# BLDC_Driver_1_1.net
KiCad netlist of a schematic drawn in Altium Designer
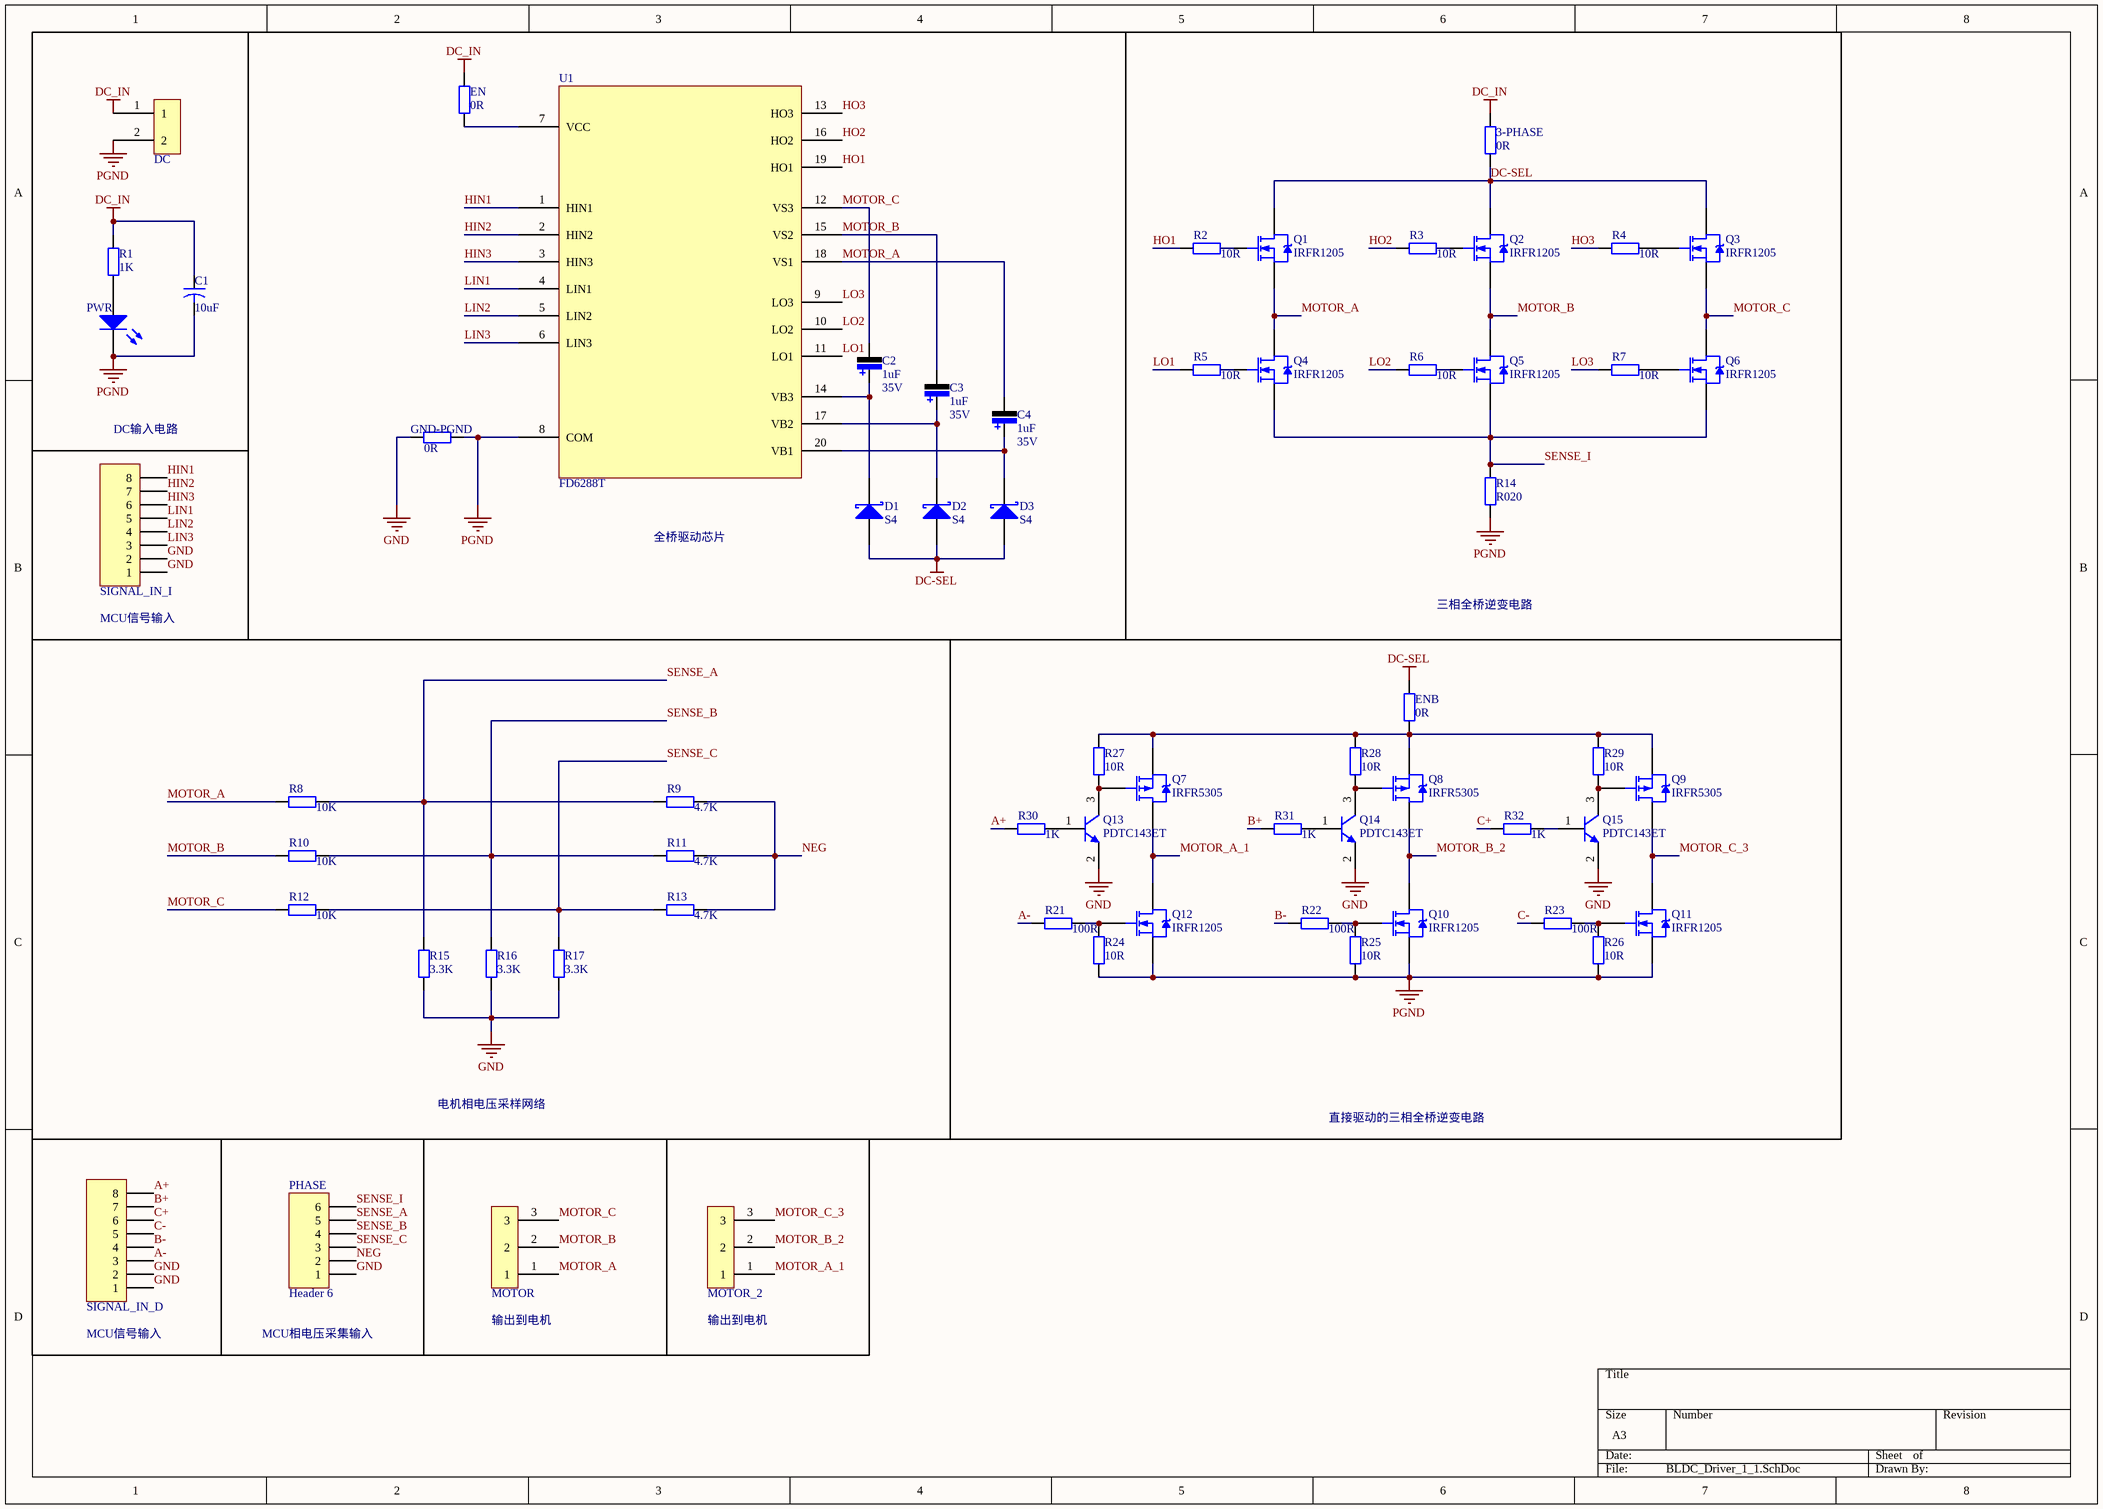
[diagram p0: BLDC_Driver_1_1.SchDoc]

(export (version "E")
  (design (tool "Eeschema 10.0.6"))
  (components
    (comp (ref "3-PHASE")
      (value "0R")
      (footprint "0805-2")
      (description "Resistor")
      (fields (field (name "Comment") "Res2") (field (name "PUBLISHER") "Altium Limited"))
      (libsource (lib "Miscellaneous Devices") (part "Res2"))
    )
    (comp (ref "C1")
      (value "10uF")
      (footprint "CAPR5-4X5")
      (description "Capacitor")
      (fields (field (name "Comment") "Cap2") (field (name "PUBLISHER") "Altium Limited"))
      (libsource (lib "Miscellaneous Devices") (part "Cap2"))
    )
    (comp (ref "C2")
      (value "1uF")
      (footprint "CAP-3216")
      (description "极性电解电容")
      (fields
        (field (name "VOL") "35V")
        (field (name "Comment") "Cap Pol")
        (field (name "PUBLISHER") "Altium Limited")
      )
      (libsource (lib "Fszhang") (part "Cap Pol"))
    )
    (comp (ref "C3")
      (value "1uF")
      (footprint "CAP-3216")
      (description "极性电解电容")
      (fields
        (field (name "VOL") "35V")
        (field (name "Comment") "Cap Pol")
        (field (name "PUBLISHER") "Altium Limited")
      )
      (libsource (lib "Fszhang") (part "Cap Pol"))
    )
    (comp (ref "C4")
      (value "1uF")
      (footprint "CAP-3216")
      (description "极性电解电容")
      (fields
        (field (name "VOL") "35V")
        (field (name "Comment") "Cap Pol")
        (field (name "PUBLISHER") "Altium Limited")
      )
      (libsource (lib "Fszhang") (part "Cap Pol"))
    )
    (comp (ref "D1")
      (value "D-Schottky")
      (footprint "DIODE-1206")
      (description "肖特基二极管")
      (fields (field (name "TYPE") "S4") (field (name "PUBLISHER") "Altium Limited"))
      (libsource (lib "Fszhang") (part "D-Schottky"))
    )
    (comp (ref "D2")
      (value "D-Schottky")
      (footprint "DIODE-1206")
      (description "肖特基二极管")
      (fields (field (name "TYPE") "S4") (field (name "PUBLISHER") "Altium Limited"))
      (libsource (lib "Fszhang") (part "D-Schottky"))
    )
    (comp (ref "D3")
      (value "D-Schottky")
      (footprint "DIODE-1206")
      (description "肖特基二极管")
      (fields (field (name "TYPE") "S4") (field (name "PUBLISHER") "Altium Limited"))
      (libsource (lib "Fszhang") (part "D-Schottky"))
    )
    (comp (ref "DC") (value "JXZ2") (footprint "JXZ2") (libsource (lib "Connector") (part "JXZ2")))
    (comp (ref "EN")
      (value "0R")
      (footprint "0805-2")
      (description "Resistor")
      (fields (field (name "Comment") "Res2") (field (name "PUBLISHER") "Altium Limited"))
      (libsource (lib "Miscellaneous Devices") (part "Res2"))
    )
    (comp (ref "ENB")
      (value "0R")
      (footprint "0805-2")
      (description "Resistor")
      (fields (field (name "Comment") "Res2") (field (name "PUBLISHER") "Altium Limited"))
      (libsource (lib "Miscellaneous Devices") (part "Res2"))
    )
    (comp (ref "GND-PGND")
      (value "0R")
      (footprint "1206")
      (description "Resistor")
      (fields (field (name "Comment") "Res2") (field (name "PUBLISHER") "Altium Limited"))
      (libsource (lib "") (part "Res2_2"))
    )
    (comp (ref "MOTOR") (value "JXZ3") (footprint "JXZ_3") (libsource (lib "Connector") (part "JXZ3")))
    (comp (ref "MOTOR_2") (value "JXZ3") (footprint "JXZ_3") (libsource (lib "Connector") (part "JXZ3")))
    (comp (ref "PHASE")
      (value "Header 6")
      (footprint "HDR1X6")
      (description "Header, 6-Pin")
      (fields (field (name "PUBLISHER") "Altium Limited"))
      (libsource (lib "Miscellaneous Connectors") (part "Header 6"))
    )
    (comp (ref "PWR")
      (value "LED2")
      (footprint "DIODE-1206")
      (description "Typical RED, GREEN, YELLOW, AMBER GaAs LED")
      (fields (field (name "PUBLISHER") "Altium Limited"))
      (libsource (lib "Miscellaneous Devices") (part "LED2"))
    )
    (comp (ref "Q1")
      (value "IRFR1205")
      (footprint "TO-252AA_N")
      (description "HEXFET Power MOSFET")
      (fields (field (name "PUBLISHER") "Altium Limited"))
      (libsource (lib "IR Discrete MOSFET - Power") (part "IRFR1205"))
    )
    (comp (ref "Q2")
      (value "IRFR1205")
      (footprint "TO-252AA_N")
      (description "HEXFET Power MOSFET")
      (fields (field (name "PUBLISHER") "Altium Limited"))
      (libsource (lib "IR Discrete MOSFET - Power") (part "IRFR1205"))
    )
    (comp (ref "Q3")
      (value "IRFR1205")
      (footprint "TO-252AA_N")
      (description "HEXFET Power MOSFET")
      (fields (field (name "PUBLISHER") "Altium Limited"))
      (libsource (lib "IR Discrete MOSFET - Power") (part "IRFR1205"))
    )
    (comp (ref "Q4")
      (value "IRFR1205")
      (footprint "TO-252AA_N")
      (description "HEXFET Power MOSFET")
      (fields (field (name "PUBLISHER") "Altium Limited"))
      (libsource (lib "IR Discrete MOSFET - Power") (part "IRFR1205"))
    )
    (comp (ref "Q5")
      (value "IRFR1205")
      (footprint "TO-252AA_N")
      (description "HEXFET Power MOSFET")
      (fields (field (name "PUBLISHER") "Altium Limited"))
      (libsource (lib "IR Discrete MOSFET - Power") (part "IRFR1205"))
    )
    (comp (ref "Q6")
      (value "IRFR1205")
      (footprint "TO-252AA_N")
      (description "HEXFET Power MOSFET")
      (fields (field (name "PUBLISHER") "Altium Limited"))
      (libsource (lib "IR Discrete MOSFET - Power") (part "IRFR1205"))
    )
    (comp (ref "Q7")
      (value "IRFR5305")
      (footprint "TO-252AA_N")
      (description "HEXFET Power MOSFET")
      (fields (field (name "PUBLISHER") "Altium Limited"))
      (libsource (lib "IR Discrete MOSFET - Power") (part "IRFR5305"))
    )
    (comp (ref "Q8")
      (value "IRFR5305")
      (footprint "TO-252AA_N")
      (description "HEXFET Power MOSFET")
      (fields (field (name "PUBLISHER") "Altium Limited"))
      (libsource (lib "IR Discrete MOSFET - Power") (part "IRFR5305"))
    )
    (comp (ref "Q9")
      (value "IRFR5305")
      (footprint "TO-252AA_N")
      (description "HEXFET Power MOSFET")
      (fields (field (name "PUBLISHER") "Altium Limited"))
      (libsource (lib "IR Discrete MOSFET - Power") (part "IRFR5305"))
    )
    (comp (ref "Q10")
      (value "IRFR1205")
      (footprint "TO-252AA_N")
      (description "HEXFET Power MOSFET")
      (fields (field (name "PUBLISHER") "Altium Limited"))
      (libsource (lib "IR Discrete MOSFET - Power") (part "IRFR1205"))
    )
    (comp (ref "Q11")
      (value "IRFR1205")
      (footprint "TO-252AA_N")
      (description "HEXFET Power MOSFET")
      (fields (field (name "PUBLISHER") "Altium Limited"))
      (libsource (lib "IR Discrete MOSFET - Power") (part "IRFR1205"))
    )
    (comp (ref "Q12")
      (value "IRFR1205")
      (footprint "TO-252AA_N")
      (description "HEXFET Power MOSFET")
      (fields (field (name "PUBLISHER") "Altium Limited"))
      (libsource (lib "IR Discrete MOSFET - Power") (part "IRFR1205"))
    )
    (comp (ref "Q13")
      (value "PDTC143ET")
      (footprint "SOT-23")
      (description "NPN贴片三极管")
      (fields (field (name "PUBLISHER") "Altium Limited"))
      (libsource (lib "Fszhang") (part "SS8050"))
    )
    (comp (ref "Q14")
      (value "PDTC143ET")
      (footprint "SOT-23")
      (description "NPN贴片三极管")
      (fields (field (name "PUBLISHER") "Altium Limited"))
      (libsource (lib "Fszhang") (part "SS8050"))
    )
    (comp (ref "Q15")
      (value "PDTC143ET")
      (footprint "SOT-23")
      (description "NPN贴片三极管")
      (fields (field (name "PUBLISHER") "Altium Limited"))
      (libsource (lib "Fszhang") (part "SS8050"))
    )
    (comp (ref "R1")
      (value "1K")
      (footprint "1206")
      (description "Resistor")
      (fields (field (name "Comment") "Res2") (field (name "PUBLISHER") "Altium Limited"))
      (libsource (lib "Miscellaneous Devices") (part "Res2"))
    )
    (comp (ref "R2")
      (value "10R")
      (footprint "1206")
      (description "Resistor")
      (fields (field (name "Comment") "Res2") (field (name "PUBLISHER") "Altium Limited"))
      (libsource (lib "") (part "Res2_1"))
    )
    (comp (ref "R3")
      (value "10R")
      (footprint "1206")
      (description "Resistor")
      (fields (field (name "Comment") "Res2") (field (name "PUBLISHER") "Altium Limited"))
      (libsource (lib "") (part "Res2_1"))
    )
    (comp (ref "R4")
      (value "10R")
      (footprint "1206")
      (description "Resistor")
      (fields (field (name "Comment") "Res2") (field (name "PUBLISHER") "Altium Limited"))
      (libsource (lib "") (part "Res2_1"))
    )
    (comp (ref "R5")
      (value "10R")
      (footprint "1206")
      (description "Resistor")
      (fields (field (name "Comment") "Res2") (field (name "PUBLISHER") "Altium Limited"))
      (libsource (lib "") (part "Res2_1"))
    )
    (comp (ref "R6")
      (value "10R")
      (footprint "1206")
      (description "Resistor")
      (fields (field (name "Comment") "Res2") (field (name "PUBLISHER") "Altium Limited"))
      (libsource (lib "") (part "Res2_1"))
    )
    (comp (ref "R7")
      (value "10R")
      (footprint "1206")
      (description "Resistor")
      (fields (field (name "Comment") "Res2") (field (name "PUBLISHER") "Altium Limited"))
      (libsource (lib "") (part "Res2_1"))
    )
    (comp (ref "R8")
      (value "10K")
      (footprint "1206")
      (description "Resistor")
      (fields (field (name "Comment") "Res2") (field (name "PUBLISHER") "Altium Limited"))
      (libsource (lib "") (part "Res2_1"))
    )
    (comp (ref "R9")
      (value "4.7K")
      (footprint "1206")
      (description "Resistor")
      (fields (field (name "Comment") "Res2") (field (name "PUBLISHER") "Altium Limited"))
      (libsource (lib "") (part "Res2_1"))
    )
    (comp (ref "R10")
      (value "10K")
      (footprint "1206")
      (description "Resistor")
      (fields (field (name "Comment") "Res2") (field (name "PUBLISHER") "Altium Limited"))
      (libsource (lib "") (part "Res2_1"))
    )
    (comp (ref "R11")
      (value "4.7K")
      (footprint "1206")
      (description "Resistor")
      (fields (field (name "Comment") "Res2") (field (name "PUBLISHER") "Altium Limited"))
      (libsource (lib "") (part "Res2_1"))
    )
    (comp (ref "R12")
      (value "10K")
      (footprint "1206")
      (description "Resistor")
      (fields (field (name "Comment") "Res2") (field (name "PUBLISHER") "Altium Limited"))
      (libsource (lib "") (part "Res2_1"))
    )
    (comp (ref "R13")
      (value "4.7K")
      (footprint "1206")
      (description "Resistor")
      (fields (field (name "Comment") "Res2") (field (name "PUBLISHER") "Altium Limited"))
      (libsource (lib "") (part "Res2_1"))
    )
    (comp (ref "R14")
      (value "R020")
      (footprint "AXIAL-0.4")
      (description "Resistor")
      (fields (field (name "Comment") "Res2") (field (name "PUBLISHER") "Altium Limited"))
      (libsource (lib "Miscellaneous Devices") (part "Res2"))
    )
    (comp (ref "R15")
      (value "3.3K")
      (footprint "1206")
      (description "Resistor")
      (fields (field (name "Comment") "Res2") (field (name "PUBLISHER") "Altium Limited"))
      (libsource (lib "Miscellaneous Devices") (part "Res2"))
    )
    (comp (ref "R16")
      (value "3.3K")
      (footprint "1206")
      (description "Resistor")
      (fields (field (name "Comment") "Res2") (field (name "PUBLISHER") "Altium Limited"))
      (libsource (lib "Miscellaneous Devices") (part "Res2"))
    )
    (comp (ref "R17")
      (value "3.3K")
      (footprint "1206")
      (description "Resistor")
      (fields (field (name "Comment") "Res2") (field (name "PUBLISHER") "Altium Limited"))
      (libsource (lib "Miscellaneous Devices") (part "Res2"))
    )
    (comp (ref "R21")
      (value "100R")
      (footprint "1206")
      (description "Resistor")
      (fields (field (name "Comment") "Res2") (field (name "PUBLISHER") "Altium Limited"))
      (libsource (lib "") (part "Res2_1"))
    )
    (comp (ref "R22")
      (value "100R")
      (footprint "1206")
      (description "Resistor")
      (fields (field (name "Comment") "Res2") (field (name "PUBLISHER") "Altium Limited"))
      (libsource (lib "") (part "Res2_1"))
    )
    (comp (ref "R23")
      (value "100R")
      (footprint "1206")
      (description "Resistor")
      (fields (field (name "Comment") "Res2") (field (name "PUBLISHER") "Altium Limited"))
      (libsource (lib "") (part "Res2_1"))
    )
    (comp (ref "R24")
      (value "10R")
      (footprint "1206")
      (description "Resistor")
      (fields (field (name "Comment") "Res2") (field (name "PUBLISHER") "Altium Limited"))
      (libsource (lib "Miscellaneous Devices") (part "Res2"))
    )
    (comp (ref "R25")
      (value "10R")
      (footprint "1206")
      (description "Resistor")
      (fields (field (name "Comment") "Res2") (field (name "PUBLISHER") "Altium Limited"))
      (libsource (lib "Miscellaneous Devices") (part "Res2"))
    )
    (comp (ref "R26")
      (value "10R")
      (footprint "1206")
      (description "Resistor")
      (fields (field (name "Comment") "Res2") (field (name "PUBLISHER") "Altium Limited"))
      (libsource (lib "Miscellaneous Devices") (part "Res2"))
    )
    (comp (ref "R27")
      (value "10R")
      (footprint "1206")
      (description "Resistor")
      (fields (field (name "Comment") "Res2") (field (name "PUBLISHER") "Altium Limited"))
      (libsource (lib "Miscellaneous Devices") (part "Res2"))
    )
    (comp (ref "R28")
      (value "10R")
      (footprint "1206")
      (description "Resistor")
      (fields (field (name "Comment") "Res2") (field (name "PUBLISHER") "Altium Limited"))
      (libsource (lib "Miscellaneous Devices") (part "Res2"))
    )
    (comp (ref "R29")
      (value "10R")
      (footprint "1206")
      (description "Resistor")
      (fields (field (name "Comment") "Res2") (field (name "PUBLISHER") "Altium Limited"))
      (libsource (lib "Miscellaneous Devices") (part "Res2"))
    )
    (comp (ref "R30")
      (value "1K")
      (footprint "1206")
      (description "Resistor")
      (fields (field (name "Comment") "Res2") (field (name "PUBLISHER") "Altium Limited"))
      (libsource (lib "") (part "Res2_1"))
    )
    (comp (ref "R31")
      (value "1K")
      (footprint "1206")
      (description "Resistor")
      (fields (field (name "Comment") "Res2") (field (name "PUBLISHER") "Altium Limited"))
      (libsource (lib "") (part "Res2_1"))
    )
    (comp (ref "R32")
      (value "1K")
      (footprint "1206")
      (description "Resistor")
      (fields (field (name "Comment") "Res2") (field (name "PUBLISHER") "Altium Limited"))
      (libsource (lib "") (part "Res2_1"))
    )
    (comp (ref "SIGNAL_IN_D")
      (value "Header 8")
      (footprint "HDR1X8")
      (description "Header, 8-Pin")
      (fields (field (name "PUBLISHER") "Altium Limited"))
      (libsource (lib "Miscellaneous Connectors") (part "Header 8"))
    )
    (comp (ref "SIGNAL_IN_I")
      (value "Header 8")
      (footprint "HDR1X8")
      (description "Header, 8-Pin")
      (fields (field (name "PUBLISHER") "Altium Limited"))
      (libsource (lib "Miscellaneous Connectors") (part "Header 8"))
    )
    (comp (ref "U1") (value "FD6288T") (footprint "TSSOP20") (libsource (lib "Connector") (part "FD6288T")))
  )
  (nets
    (net (code "1") (name "/A+") (class "Default")
      (node (ref "R30") (pin "1") (pinfunction "1_1") (pintype "passive"))
      (node (ref "SIGNAL_IN_D") (pin "8") (pinfunction "8_8") (pintype "passive"))
    )
    (net (code "2") (name "/A-") (class "Default")
      (node (ref "R21") (pin "1") (pinfunction "1_1") (pintype "passive"))
      (node (ref "SIGNAL_IN_D") (pin "3") (pinfunction "3_3") (pintype "passive"))
    )
    (net (code "3") (name "/B+") (class "Default")
      (node (ref "R31") (pin "1") (pinfunction "1_1") (pintype "passive"))
      (node (ref "SIGNAL_IN_D") (pin "7") (pinfunction "7_7") (pintype "passive"))
    )
    (net (code "4") (name "/B-") (class "Default")
      (node (ref "R22") (pin "1") (pinfunction "1_1") (pintype "passive"))
      (node (ref "SIGNAL_IN_D") (pin "4") (pinfunction "4_4") (pintype "passive"))
    )
    (net (code "5") (name "/C+") (class "Default")
      (node (ref "R32") (pin "1") (pinfunction "1_1") (pintype "passive"))
      (node (ref "SIGNAL_IN_D") (pin "6") (pinfunction "6_6") (pintype "passive"))
    )
    (net (code "6") (name "/C-") (class "Default")
      (node (ref "R23") (pin "1") (pinfunction "1_1") (pintype "passive"))
      (node (ref "SIGNAL_IN_D") (pin "5") (pinfunction "5_5") (pintype "passive"))
    )
    (net (code "7") (name "/HIN1") (class "Default")
      (node (ref "SIGNAL_IN_I") (pin "8") (pinfunction "8_8") (pintype "passive"))
      (node (ref "U1") (pin "1") (pinfunction "HIN1_1") (pintype "passive"))
    )
    (net (code "8") (name "/HIN2") (class "Default")
      (node (ref "SIGNAL_IN_I") (pin "7") (pinfunction "7_7") (pintype "passive"))
      (node (ref "U1") (pin "2") (pinfunction "HIN2_2") (pintype "passive"))
    )
    (net (code "9") (name "/HIN3") (class "Default")
      (node (ref "SIGNAL_IN_I") (pin "6") (pinfunction "6_6") (pintype "passive"))
      (node (ref "U1") (pin "3") (pinfunction "HIN3_3") (pintype "passive"))
    )
    (net (code "10") (name "/HO1") (class "Default")
      (node (ref "R2") (pin "1") (pinfunction "1_1") (pintype "passive"))
      (node (ref "U1") (pin "19") (pinfunction "HO1_19") (pintype "passive"))
    )
    (net (code "11") (name "/HO2") (class "Default")
      (node (ref "R3") (pin "1") (pinfunction "1_1") (pintype "passive"))
      (node (ref "U1") (pin "16") (pinfunction "HO2_16") (pintype "passive"))
    )
    (net (code "12") (name "/HO3") (class "Default")
      (node (ref "R4") (pin "1") (pinfunction "1_1") (pintype "passive"))
      (node (ref "U1") (pin "13") (pinfunction "HO3_13") (pintype "passive"))
    )
    (net (code "13") (name "/LIN1") (class "Default")
      (node (ref "SIGNAL_IN_I") (pin "5") (pinfunction "5_5") (pintype "passive"))
      (node (ref "U1") (pin "4") (pinfunction "LIN1_4") (pintype "passive"))
    )
    (net (code "14") (name "/LIN2") (class "Default")
      (node (ref "SIGNAL_IN_I") (pin "4") (pinfunction "4_4") (pintype "passive"))
      (node (ref "U1") (pin "5") (pinfunction "LIN2_5") (pintype "passive"))
    )
    (net (code "15") (name "/LIN3") (class "Default")
      (node (ref "SIGNAL_IN_I") (pin "3") (pinfunction "3_3") (pintype "passive"))
      (node (ref "U1") (pin "6") (pinfunction "LIN3_6") (pintype "passive"))
    )
    (net (code "16") (name "/LO1") (class "Default")
      (node (ref "R5") (pin "1") (pinfunction "1_1") (pintype "passive"))
      (node (ref "U1") (pin "11") (pinfunction "LO1_11") (pintype "passive"))
    )
    (net (code "17") (name "/LO2") (class "Default")
      (node (ref "R6") (pin "1") (pinfunction "1_1") (pintype "passive"))
      (node (ref "U1") (pin "10") (pinfunction "LO2_10") (pintype "passive"))
    )
    (net (code "18") (name "/LO3") (class "Default")
      (node (ref "R7") (pin "1") (pinfunction "1_1") (pintype "passive"))
      (node (ref "U1") (pin "9") (pinfunction "LO3_9") (pintype "passive"))
    )
    (net (code "19") (name "/MOTOR_A") (class "Default")
      (node (ref "C4") (pin "2") (pinfunction "2_2") (pintype "passive"))
      (node (ref "MOTOR") (pin "1") (pinfunction "1_1") (pintype "passive"))
      (node (ref "Q1") (pin "3") (pinfunction "S_3") (pintype "passive"))
      (node (ref "Q4") (pin "4") (pinfunction "D_4") (pintype "passive"))
      (node (ref "R8") (pin "1") (pinfunction "1_1") (pintype "passive"))
      (node (ref "U1") (pin "18") (pinfunction "VS1_18") (pintype "passive"))
    )
    (net (code "20") (name "/MOTOR_A_1") (class "Default")
      (node (ref "MOTOR_2") (pin "1") (pinfunction "1_1") (pintype "passive"))
      (node (ref "Q12") (pin "4") (pinfunction "D_4") (pintype "passive"))
      (node (ref "Q7") (pin "4") (pinfunction "D_4") (pintype "passive"))
    )
    (net (code "21") (name "/MOTOR_B") (class "Default")
      (node (ref "C3") (pin "2") (pinfunction "2_2") (pintype "passive"))
      (node (ref "MOTOR") (pin "2") (pinfunction "2_2") (pintype "passive"))
      (node (ref "Q2") (pin "3") (pinfunction "S_3") (pintype "passive"))
      (node (ref "Q5") (pin "4") (pinfunction "D_4") (pintype "passive"))
      (node (ref "R10") (pin "1") (pinfunction "1_1") (pintype "passive"))
      (node (ref "U1") (pin "15") (pinfunction "VS2_15") (pintype "passive"))
    )
    (net (code "22") (name "/MOTOR_B_2") (class "Default")
      (node (ref "MOTOR_2") (pin "2") (pinfunction "2_2") (pintype "passive"))
      (node (ref "Q10") (pin "4") (pinfunction "D_4") (pintype "passive"))
      (node (ref "Q8") (pin "4") (pinfunction "D_4") (pintype "passive"))
    )
    (net (code "23") (name "/MOTOR_C") (class "Default")
      (node (ref "C2") (pin "2") (pinfunction "2_2") (pintype "passive"))
      (node (ref "MOTOR") (pin "3") (pinfunction "3_3") (pintype "passive"))
      (node (ref "Q3") (pin "3") (pinfunction "S_3") (pintype "passive"))
      (node (ref "Q6") (pin "4") (pinfunction "D_4") (pintype "passive"))
      (node (ref "R12") (pin "1") (pinfunction "1_1") (pintype "passive"))
      (node (ref "U1") (pin "12") (pinfunction "VS3_12") (pintype "passive"))
    )
    (net (code "24") (name "/MOTOR_C_3") (class "Default")
      (node (ref "MOTOR_2") (pin "3") (pinfunction "3_3") (pintype "passive"))
      (node (ref "Q11") (pin "4") (pinfunction "D_4") (pintype "passive"))
      (node (ref "Q9") (pin "4") (pinfunction "D_4") (pintype "passive"))
    )
    (net (code "25") (name "/NEG") (class "Default")
      (node (ref "PHASE") (pin "2") (pinfunction "2_2") (pintype "passive"))
      (node (ref "R11") (pin "2") (pinfunction "2_2") (pintype "passive"))
      (node (ref "R13") (pin "2") (pinfunction "2_2") (pintype "passive"))
      (node (ref "R9") (pin "2") (pinfunction "2_2") (pintype "passive"))
    )
    (net (code "26") (name "/SENSE_A") (class "Default")
      (node (ref "PHASE") (pin "5") (pinfunction "5_5") (pintype "passive"))
      (node (ref "R15") (pin "2") (pinfunction "2_2") (pintype "passive"))
      (node (ref "R8") (pin "2") (pinfunction "2_2") (pintype "passive"))
      (node (ref "R9") (pin "1") (pinfunction "1_1") (pintype "passive"))
    )
    (net (code "27") (name "/SENSE_B") (class "Default")
      (node (ref "PHASE") (pin "4") (pinfunction "4_4") (pintype "passive"))
      (node (ref "R10") (pin "2") (pinfunction "2_2") (pintype "passive"))
      (node (ref "R11") (pin "1") (pinfunction "1_1") (pintype "passive"))
      (node (ref "R16") (pin "2") (pinfunction "2_2") (pintype "passive"))
    )
    (net (code "28") (name "/SENSE_C") (class "Default")
      (node (ref "PHASE") (pin "3") (pinfunction "3_3") (pintype "passive"))
      (node (ref "R12") (pin "2") (pinfunction "2_2") (pintype "passive"))
      (node (ref "R13") (pin "1") (pinfunction "1_1") (pintype "passive"))
      (node (ref "R17") (pin "2") (pinfunction "2_2") (pintype "passive"))
    )
    (net (code "29") (name "/SENSE_I") (class "Default")
      (node (ref "PHASE") (pin "6") (pinfunction "6_6") (pintype "passive"))
      (node (ref "Q4") (pin "3") (pinfunction "S_3") (pintype "passive"))
      (node (ref "Q5") (pin "3") (pinfunction "S_3") (pintype "passive"))
      (node (ref "Q6") (pin "3") (pinfunction "S_3") (pintype "passive"))
      (node (ref "R14") (pin "2") (pinfunction "2_2") (pintype "passive"))
    )
    (net (code "30") (name "DC-SEL") (class "Default")
      (node (ref "3-PHASE") (pin "1") (pinfunction "1_1") (pintype "passive"))
      (node (ref "D1") (pin "1") (pinfunction "A_1") (pintype "passive"))
      (node (ref "D2") (pin "1") (pinfunction "A_1") (pintype "passive"))
      (node (ref "D3") (pin "1") (pinfunction "A_1") (pintype "passive"))
      (node (ref "ENB") (pin "2") (pinfunction "2_2") (pintype "passive"))
      (node (ref "Q1") (pin "4") (pinfunction "D_4") (pintype "passive"))
      (node (ref "Q2") (pin "4") (pinfunction "D_4") (pintype "passive"))
      (node (ref "Q3") (pin "4") (pinfunction "D_4") (pintype "passive"))
    )
    (net (code "31") (name "DC_IN") (class "Default")
      (node (ref "3-PHASE") (pin "2") (pinfunction "2_2") (pintype "passive"))
      (node (ref "C1") (pin "1") (pinfunction "1_1") (pintype "passive"))
      (node (ref "DC") (pin "1") (pinfunction "1_1") (pintype "passive"))
      (node (ref "EN") (pin "2") (pinfunction "2_2") (pintype "passive"))
      (node (ref "R1") (pin "2") (pinfunction "2_2") (pintype "passive"))
    )
    (net (code "32") (name "GND") (class "Default")
      (node (ref "GND-PGND") (pin "2") (pinfunction "2_2") (pintype "passive"))
      (node (ref "PHASE") (pin "1") (pinfunction "1_1") (pintype "passive"))
      (node (ref "Q13") (pin "2") (pinfunction "E_2") (pintype "passive"))
      (node (ref "Q14") (pin "2") (pinfunction "E_2") (pintype "passive"))
      (node (ref "Q15") (pin "2") (pinfunction "E_2") (pintype "passive"))
      (node (ref "R15") (pin "1") (pinfunction "1_1") (pintype "passive"))
      (node (ref "R16") (pin "1") (pinfunction "1_1") (pintype "passive"))
      (node (ref "R17") (pin "1") (pinfunction "1_1") (pintype "passive"))
      (node (ref "SIGNAL_IN_D") (pin "1") (pinfunction "1_1") (pintype "passive"))
      (node (ref "SIGNAL_IN_D") (pin "2") (pinfunction "2_2") (pintype "passive"))
      (node (ref "SIGNAL_IN_I") (pin "1") (pinfunction "1_1") (pintype "passive"))
      (node (ref "SIGNAL_IN_I") (pin "2") (pinfunction "2_2") (pintype "passive"))
    )
    (net (code "33") (name "Net-(D1-K)") (class "Default")
      (node (ref "C2") (pin "1") (pinfunction "1_1") (pintype "passive"))
      (node (ref "D1") (pin "2") (pinfunction "K_2") (pintype "passive"))
      (node (ref "U1") (pin "14") (pinfunction "VB3_14") (pintype "passive"))
    )
    (net (code "34") (name "Net-(D2-K)") (class "Default")
      (node (ref "C3") (pin "1") (pinfunction "1_1") (pintype "passive"))
      (node (ref "D2") (pin "2") (pinfunction "K_2") (pintype "passive"))
      (node (ref "U1") (pin "17") (pinfunction "VB2_17") (pintype "passive"))
    )
    (net (code "35") (name "Net-(D3-K)") (class "Default")
      (node (ref "C4") (pin "1") (pinfunction "1_1") (pintype "passive"))
      (node (ref "D3") (pin "2") (pinfunction "K_2") (pintype "passive"))
      (node (ref "U1") (pin "20") (pinfunction "VB1_20") (pintype "passive"))
    )
    (net (code "36") (name "Net-(PWR-A)") (class "Default")
      (node (ref "PWR") (pin "1") (pinfunction "A_1") (pintype "passive"))
      (node (ref "R1") (pin "1") (pinfunction "1_1") (pintype "passive"))
    )
    (net (code "37") (name "Net-(Q1-G)") (class "Default")
      (node (ref "Q1") (pin "1") (pinfunction "G_1") (pintype "passive"))
      (node (ref "R2") (pin "2") (pinfunction "2_2") (pintype "passive"))
    )
    (net (code "38") (name "Net-(Q2-G)") (class "Default")
      (node (ref "Q2") (pin "1") (pinfunction "G_1") (pintype "passive"))
      (node (ref "R3") (pin "2") (pinfunction "2_2") (pintype "passive"))
    )
    (net (code "39") (name "Net-(Q3-G)") (class "Default")
      (node (ref "Q3") (pin "1") (pinfunction "G_1") (pintype "passive"))
      (node (ref "R4") (pin "2") (pinfunction "2_2") (pintype "passive"))
    )
    (net (code "40") (name "Net-(Q4-G)") (class "Default")
      (node (ref "Q4") (pin "1") (pinfunction "G_1") (pintype "passive"))
      (node (ref "R5") (pin "2") (pinfunction "2_2") (pintype "passive"))
    )
    (net (code "41") (name "Net-(Q5-G)") (class "Default")
      (node (ref "Q5") (pin "1") (pinfunction "G_1") (pintype "passive"))
      (node (ref "R6") (pin "2") (pinfunction "2_2") (pintype "passive"))
    )
    (net (code "42") (name "Net-(Q6-G)") (class "Default")
      (node (ref "Q6") (pin "1") (pinfunction "G_1") (pintype "passive"))
      (node (ref "R7") (pin "2") (pinfunction "2_2") (pintype "passive"))
    )
    (net (code "43") (name "Net-(Q7-S)") (class "Default")
      (node (ref "ENB") (pin "1") (pinfunction "1_1") (pintype "passive"))
      (node (ref "Q7") (pin "3") (pinfunction "S_3") (pintype "passive"))
      (node (ref "Q8") (pin "3") (pinfunction "S_3") (pintype "passive"))
      (node (ref "Q9") (pin "3") (pinfunction "S_3") (pintype "passive"))
      (node (ref "R27") (pin "2") (pinfunction "2_2") (pintype "passive"))
      (node (ref "R28") (pin "2") (pinfunction "2_2") (pintype "passive"))
      (node (ref "R29") (pin "2") (pinfunction "2_2") (pintype "passive"))
    )
    (net (code "44") (name "Net-(Q10-G)") (class "Default")
      (node (ref "Q10") (pin "1") (pinfunction "G_1") (pintype "passive"))
      (node (ref "R22") (pin "2") (pinfunction "2_2") (pintype "passive"))
      (node (ref "R25") (pin "2") (pinfunction "2_2") (pintype "passive"))
    )
    (net (code "45") (name "Net-(Q11-G)") (class "Default")
      (node (ref "Q11") (pin "1") (pinfunction "G_1") (pintype "passive"))
      (node (ref "R23") (pin "2") (pinfunction "2_2") (pintype "passive"))
      (node (ref "R26") (pin "2") (pinfunction "2_2") (pintype "passive"))
    )
    (net (code "46") (name "Net-(Q12-G)") (class "Default")
      (node (ref "Q12") (pin "1") (pinfunction "G_1") (pintype "passive"))
      (node (ref "R21") (pin "2") (pinfunction "2_2") (pintype "passive"))
      (node (ref "R24") (pin "2") (pinfunction "2_2") (pintype "passive"))
    )
    (net (code "47") (name "Net-(Q13-B)") (class "Default")
      (node (ref "Q13") (pin "1") (pinfunction "B_1") (pintype "passive"))
      (node (ref "R30") (pin "2") (pinfunction "2_2") (pintype "passive"))
    )
    (net (code "48") (name "Net-(Q13-C)") (class "Default")
      (node (ref "Q13") (pin "3") (pinfunction "C_3") (pintype "passive"))
      (node (ref "Q7") (pin "1") (pinfunction "G_1") (pintype "passive"))
      (node (ref "R27") (pin "1") (pinfunction "1_1") (pintype "passive"))
    )
    (net (code "49") (name "Net-(Q14-B)") (class "Default")
      (node (ref "Q14") (pin "1") (pinfunction "B_1") (pintype "passive"))
      (node (ref "R31") (pin "2") (pinfunction "2_2") (pintype "passive"))
    )
    (net (code "50") (name "Net-(Q14-C)") (class "Default")
      (node (ref "Q14") (pin "3") (pinfunction "C_3") (pintype "passive"))
      (node (ref "Q8") (pin "1") (pinfunction "G_1") (pintype "passive"))
      (node (ref "R28") (pin "1") (pinfunction "1_1") (pintype "passive"))
    )
    (net (code "51") (name "Net-(Q15-B)") (class "Default")
      (node (ref "Q15") (pin "1") (pinfunction "B_1") (pintype "passive"))
      (node (ref "R32") (pin "2") (pinfunction "2_2") (pintype "passive"))
    )
    (net (code "52") (name "Net-(Q15-C)") (class "Default")
      (node (ref "Q15") (pin "3") (pinfunction "C_3") (pintype "passive"))
      (node (ref "Q9") (pin "1") (pinfunction "G_1") (pintype "passive"))
      (node (ref "R29") (pin "1") (pinfunction "1_1") (pintype "passive"))
    )
    (net (code "53") (name "Net-(U1-VCC)") (class "Default")
      (node (ref "EN") (pin "1") (pinfunction "1_1") (pintype "passive"))
      (node (ref "U1") (pin "7") (pinfunction "VCC_7") (pintype "passive"))
    )
    (net (code "54") (name "PGND") (class "Default")
      (node (ref "C1") (pin "2") (pinfunction "2_2") (pintype "passive"))
      (node (ref "DC") (pin "2") (pinfunction "2_2") (pintype "passive"))
      (node (ref "GND-PGND") (pin "1") (pinfunction "1_1") (pintype "passive"))
      (node (ref "PWR") (pin "2") (pinfunction "K_2") (pintype "passive"))
      (node (ref "Q10") (pin "3") (pinfunction "S_3") (pintype "passive"))
      (node (ref "Q11") (pin "3") (pinfunction "S_3") (pintype "passive"))
      (node (ref "Q12") (pin "3") (pinfunction "S_3") (pintype "passive"))
      (node (ref "R14") (pin "1") (pinfunction "1_1") (pintype "passive"))
      (node (ref "R24") (pin "1") (pinfunction "1_1") (pintype "passive"))
      (node (ref "R25") (pin "1") (pinfunction "1_1") (pintype "passive"))
      (node (ref "R26") (pin "1") (pinfunction "1_1") (pintype "passive"))
      (node (ref "U1") (pin "8") (pinfunction "COM_8") (pintype "passive"))
    )
  )
)
